# Micro-SD-Card-Adapter.net
KiCad netlist of a schematic drawn in EasyEDA Pro
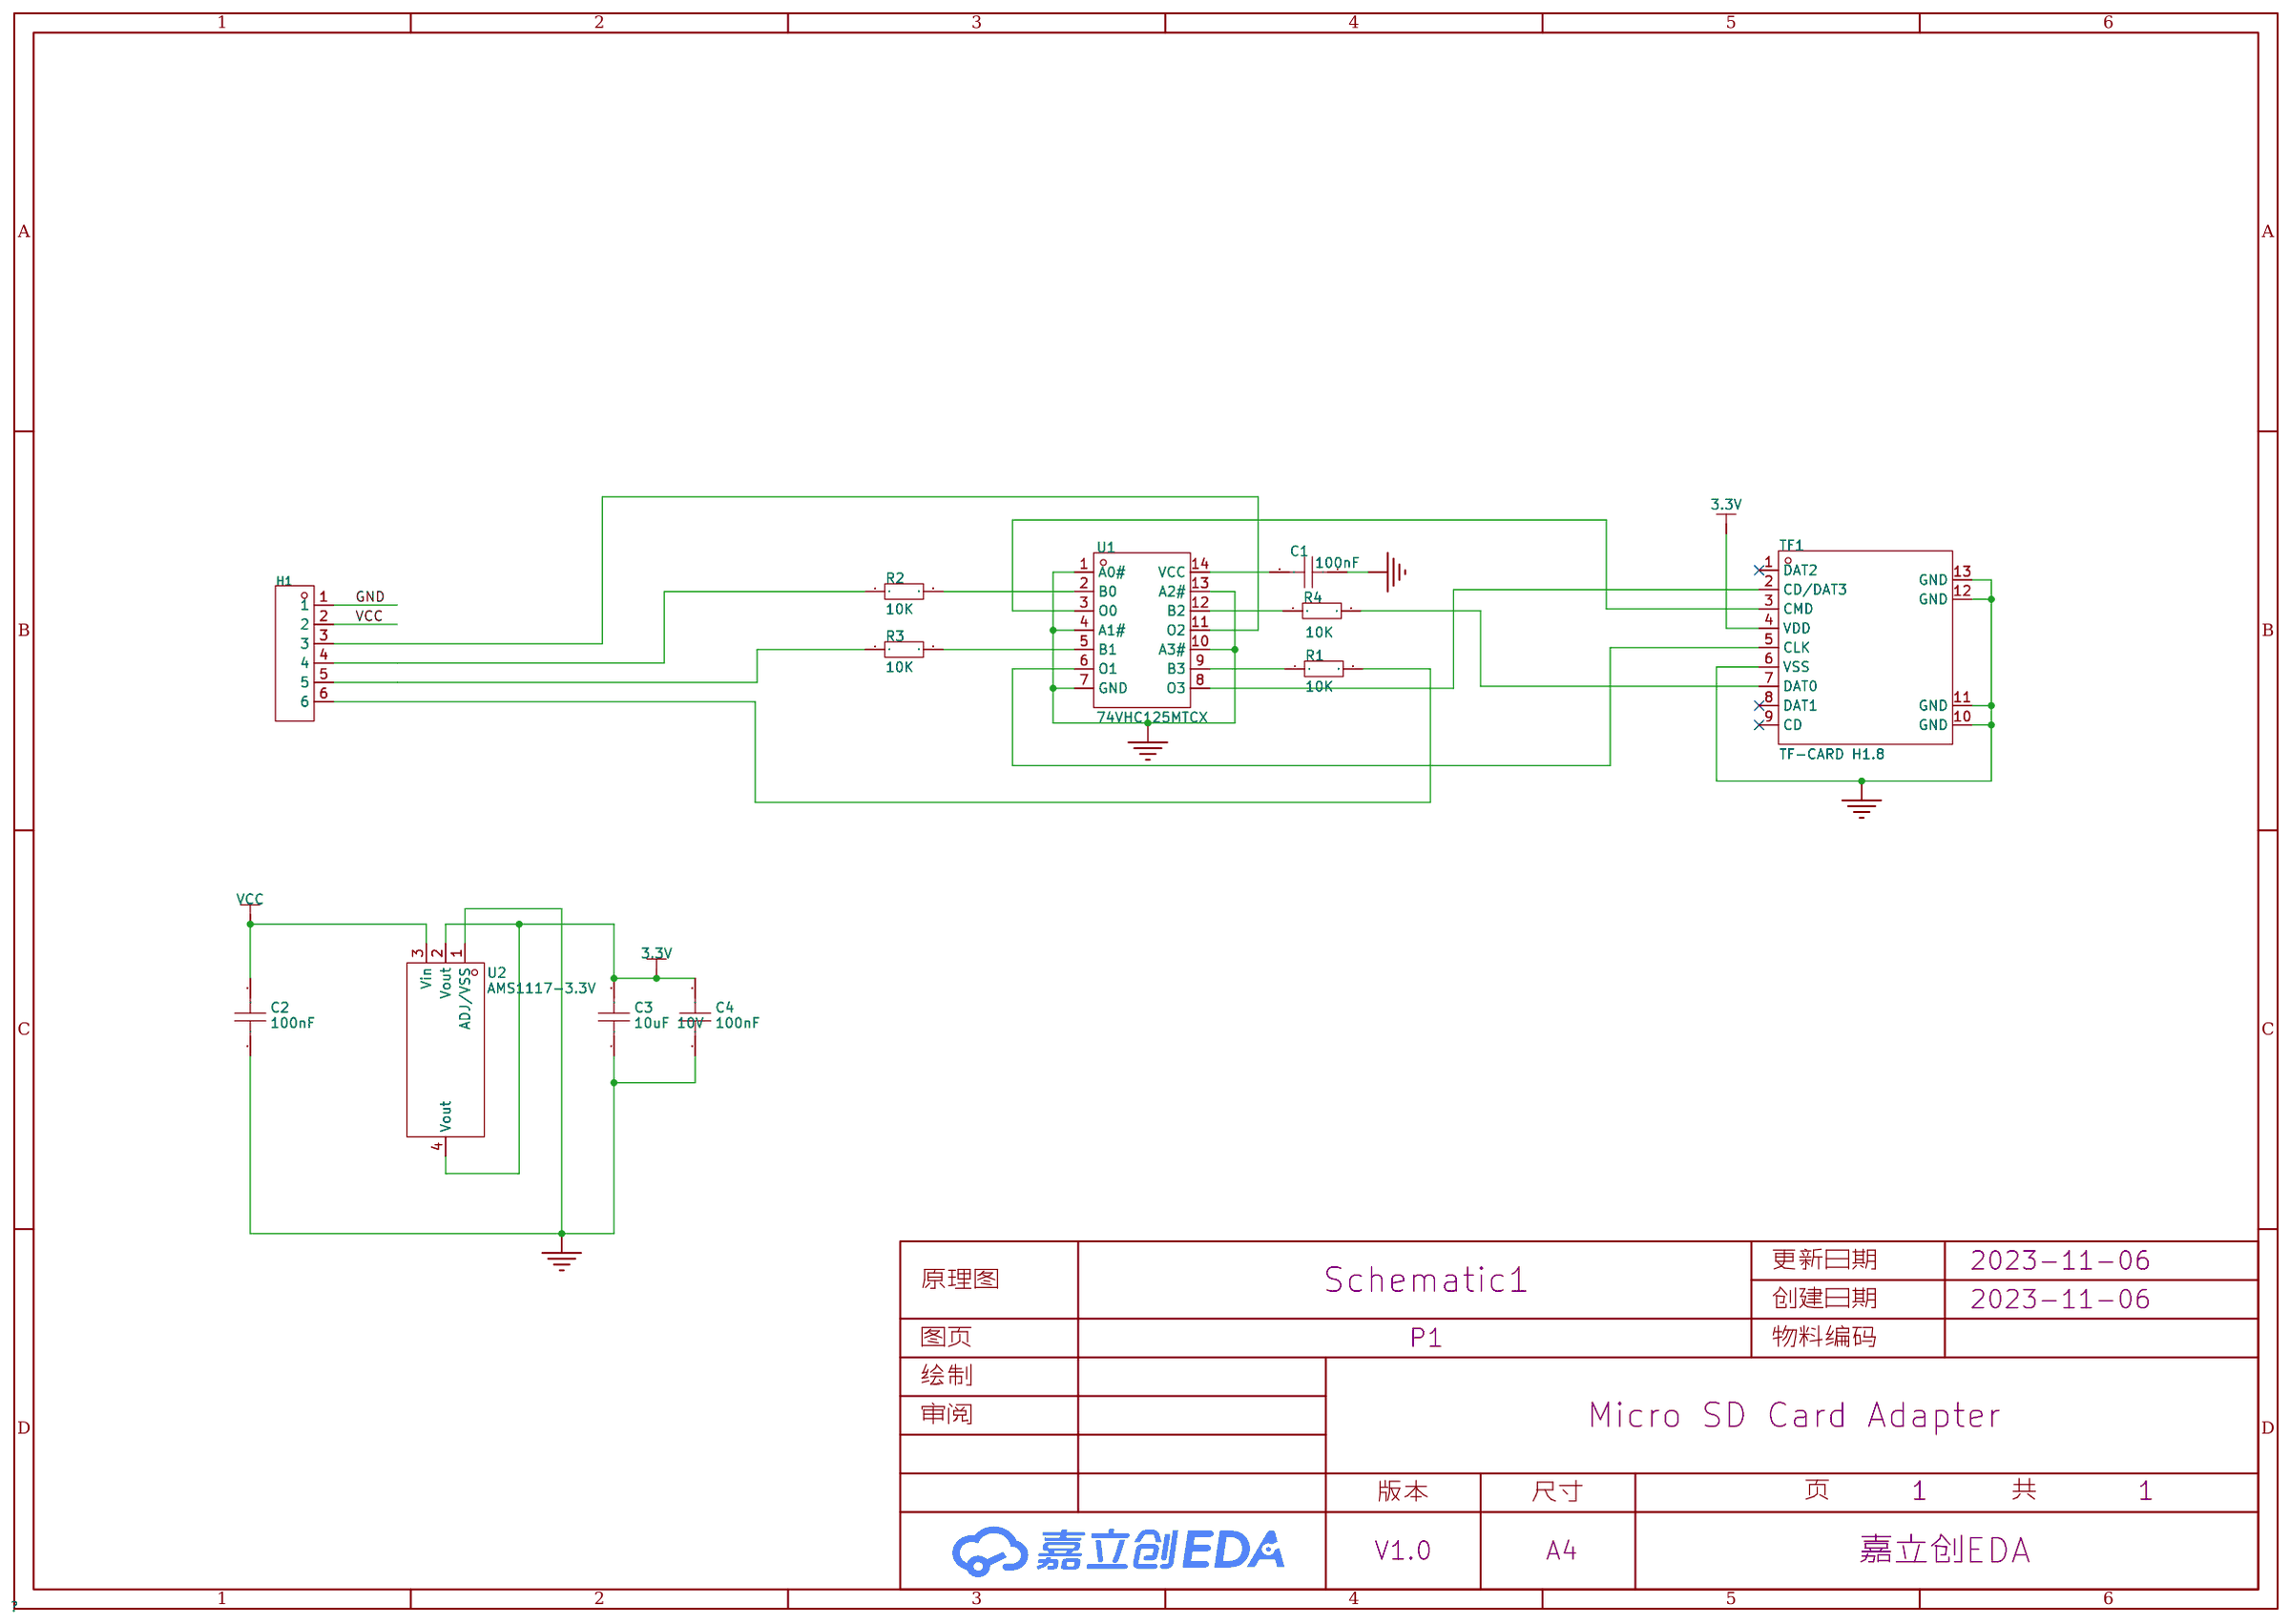
[diagram p0: schematic sheet]

(export (version "E")
  (design (tool "Eeschema 10.0.6"))
  (components
    (comp (ref "C1")
      (value "100nF")
      (footprint "easyedapro:C0603")
      (libsource (lib "easyedapro") (part "CapAcitance"))
    )
    (comp (ref "C2")
      (value "100nF")
      (footprint "easyedapro:C0603")
      (libsource (lib "easyedapro") (part "CapAcitance"))
    )
    (comp (ref "C3")
      (value "10uF 10V")
      (footprint "easyedapro:C0603")
      (libsource (lib "easyedapro") (part "CapAcitance"))
    )
    (comp (ref "C4")
      (value "100nF")
      (footprint "easyedapro:C0603")
      (libsource (lib "easyedapro") (part "CapAcitance"))
    )
    (comp (ref "H1")
      (value "~")
      (footprint "easyedapro:HDR-TH_6P-P2.54-V-F")
      (libsource (lib "easyedapro") (part "Header-Female-2.54_1x6"))
    )
    (comp (ref "R1") (value "10K") (footprint "easyedapro:R0603") (libsource (lib "easyedapro") (part "电阻")))
    (comp (ref "R2") (value "10K") (footprint "easyedapro:R0603") (libsource (lib "easyedapro") (part "电阻")))
    (comp (ref "R3") (value "10K") (footprint "easyedapro:R0603") (libsource (lib "easyedapro") (part "电阻")))
    (comp (ref "R4") (value "10K") (footprint "easyedapro:R0603") (libsource (lib "easyedapro") (part "电阻")))
    (comp (ref "TF1")
      (value "TF-CARD H1.8")
      (footprint "easyedapro:TF-SMD_TF-CARD-H1.8")
      (description "卡连接方式:自弹式;卡类型:MicroSD卡(TF卡);连接器类型:卡座;本体最大高度:1.8mm;触头材质:铜合金;触头镀层:金;工作温度范围:-40°C~+70°C;")
      (fields (field (name "Manufacturer") "SHOU HAN(首韩)"))
      (libsource (lib "easyedapro") (part "TF-CARD H1.8"))
    )
    (comp (ref "U1")
      (value "74VHC125MTCX")
      (footprint "easyedapro:TSSOP-14_L5.0-W4.4-P0.65-LS6.5-BL")
      (description "74VHC Series High Speed Quad Buffer w/ 3-STATE Output - TSSOP-14")
      (fields (field (name "Manufacturer") "onsemi(安森美)"))
      (libsource (lib "easyedapro") (part "74VHC125MTCX"))
    )
    (comp (ref "U2")
      (value "AMS1117-3.3V")
      (footprint "easyedapro:SOT-223-3_L6.5-W3.4-P2.30-LS7.0-BR")
      (description "最大输入电压:18V;输出电压:3.3V;输出电流:800mA;")
      (fields (field (name "Manufacturer") "JSMSEMI(杰盛微)"))
      (libsource (lib "easyedapro") (part "AMS1117-3.3V_C5205141"))
    )
  )
  (nets
    (net (code "1") (name "3.3V") (class "Default")
      (node (ref "C3") (pin "2") (pinfunction "2_2") (pintype "input"))
      (node (ref "C4") (pin "2") (pinfunction "2_2") (pintype "input"))
      (node (ref "TF1") (pin "4") (pinfunction "VDD_4") (pintype "unspecified"))
      (node (ref "U2") (pin "2") (pinfunction "Vout_2") (pintype "input"))
      (node (ref "U2") (pin "4") (pinfunction "Vout_4") (pintype "input"))
    )
    (net (code "2") (name "GND") (class "Default")
      (node (ref "C1") (pin "1") (pinfunction "1_1") (pintype "input"))
      (node (ref "C2") (pin "1") (pinfunction "1_1") (pintype "input"))
      (node (ref "C3") (pin "1") (pinfunction "1_1") (pintype "input"))
      (node (ref "C4") (pin "1") (pinfunction "1_1") (pintype "input"))
      (node (ref "H1") (pin "1") (pinfunction "1_1") (pintype "input"))
      (node (ref "TF1") (pin "10") (pinfunction "GND_10") (pintype "unspecified"))
      (node (ref "TF1") (pin "11") (pinfunction "GND_11") (pintype "unspecified"))
      (node (ref "TF1") (pin "12") (pinfunction "GND_12") (pintype "unspecified"))
      (node (ref "TF1") (pin "13") (pinfunction "GND_13") (pintype "unspecified"))
      (node (ref "TF1") (pin "6") (pinfunction "VSS_6") (pintype "unspecified"))
      (node (ref "U1") (pin "1") (pinfunction "A0#_1") (pintype "input"))
      (node (ref "U1") (pin "10") (pinfunction "A3#_10") (pintype "input"))
      (node (ref "U1") (pin "13") (pinfunction "A2#_13") (pintype "input"))
      (node (ref "U1") (pin "4") (pinfunction "A1#_4") (pintype "input"))
      (node (ref "U1") (pin "7") (pinfunction "GND_7") (pintype "input"))
      (node (ref "U2") (pin "1") (pinfunction "ADJ/VSS_1") (pintype "input"))
    )
    (net (code "3") (name "Net-(H1-Pad4)") (class "Default")
      (node (ref "H1") (pin "4") (pinfunction "4_4") (pintype "input"))
      (node (ref "R2") (pin "1") (pinfunction "1_1") (pintype "input"))
    )
    (net (code "4") (name "Net-(H1-Pad5)") (class "Default")
      (node (ref "H1") (pin "5") (pinfunction "5_5") (pintype "input"))
      (node (ref "R3") (pin "1") (pinfunction "1_1") (pintype "input"))
    )
    (net (code "5") (name "Net-(H1-Pad6)") (class "Default")
      (node (ref "H1") (pin "6") (pinfunction "6_6") (pintype "input"))
      (node (ref "R1") (pin "2") (pinfunction "2_2") (pintype "input"))
    )
    (net (code "6") (name "Net-(TF1-CD{slash}DAT3)") (class "Default")
      (node (ref "TF1") (pin "2") (pinfunction "CD/DAT3_2") (pintype "unspecified"))
      (node (ref "U1") (pin "8") (pinfunction "O3_8") (pintype "input"))
    )
    (net (code "7") (name "Net-(TF1-CLK)") (class "Default")
      (node (ref "TF1") (pin "5") (pinfunction "CLK_5") (pintype "unspecified"))
      (node (ref "U1") (pin "6") (pinfunction "O1_6") (pintype "input"))
    )
    (net (code "8") (name "Net-(TF1-CMD)") (class "Default")
      (node (ref "TF1") (pin "3") (pinfunction "CMD_3") (pintype "unspecified"))
      (node (ref "U1") (pin "3") (pinfunction "O0_3") (pintype "input"))
    )
    (net (code "9") (name "Net-(TF1-DAT0)") (class "Default")
      (node (ref "R4") (pin "2") (pinfunction "2_2") (pintype "input"))
      (node (ref "TF1") (pin "7") (pinfunction "DAT0_7") (pintype "unspecified"))
    )
    (net (code "10") (name "Net-(U1-B0)") (class "Default")
      (node (ref "R2") (pin "2") (pinfunction "2_2") (pintype "input"))
      (node (ref "U1") (pin "2") (pinfunction "B0_2") (pintype "input"))
    )
    (net (code "11") (name "Net-(U1-B1)") (class "Default")
      (node (ref "R3") (pin "2") (pinfunction "2_2") (pintype "input"))
      (node (ref "U1") (pin "5") (pinfunction "B1_5") (pintype "input"))
    )
    (net (code "12") (name "Net-(U1-B2)") (class "Default")
      (node (ref "R4") (pin "1") (pinfunction "1_1") (pintype "input"))
      (node (ref "U1") (pin "12") (pinfunction "B2_12") (pintype "input"))
    )
    (net (code "13") (name "Net-(U1-B3)") (class "Default")
      (node (ref "R1") (pin "1") (pinfunction "1_1") (pintype "input"))
      (node (ref "U1") (pin "9") (pinfunction "B3_9") (pintype "input"))
    )
    (net (code "14") (name "Net-(U1-O2)") (class "Default")
      (node (ref "H1") (pin "3") (pinfunction "3_3") (pintype "input"))
      (node (ref "U1") (pin "11") (pinfunction "O2_11") (pintype "input"))
    )
    (net (code "15") (name "Net-(U1-VCC)") (class "Default")
      (node (ref "C1") (pin "2") (pinfunction "2_2") (pintype "input"))
      (node (ref "U1") (pin "14") (pinfunction "VCC_14") (pintype "input"))
    )
    (net (code "16") (name "VCC") (class "Default")
      (node (ref "C2") (pin "2") (pinfunction "2_2") (pintype "input"))
      (node (ref "H1") (pin "2") (pinfunction "2_2") (pintype "input"))
      (node (ref "U2") (pin "3") (pinfunction "Vin_3") (pintype "input"))
    )
    (net (code "17") (name "unconnected-(TF1-CD-Pad9)") (class "Default")
      (node (ref "TF1") (pin "9") (pinfunction "CD_9") (pintype "unspecified+no_connect"))
    )
    (net (code "18") (name "unconnected-(TF1-DAT1-Pad8)") (class "Default")
      (node (ref "TF1") (pin "8") (pinfunction "DAT1_8") (pintype "unspecified+no_connect"))
    )
    (net (code "19") (name "unconnected-(TF1-DAT2-Pad1)") (class "Default")
      (node (ref "TF1") (pin "1") (pinfunction "DAT2_1") (pintype "unspecified+no_connect"))
    )
  )
)
